# V_15.net
KiCad netlist of a schematic drawn in Altium Designer
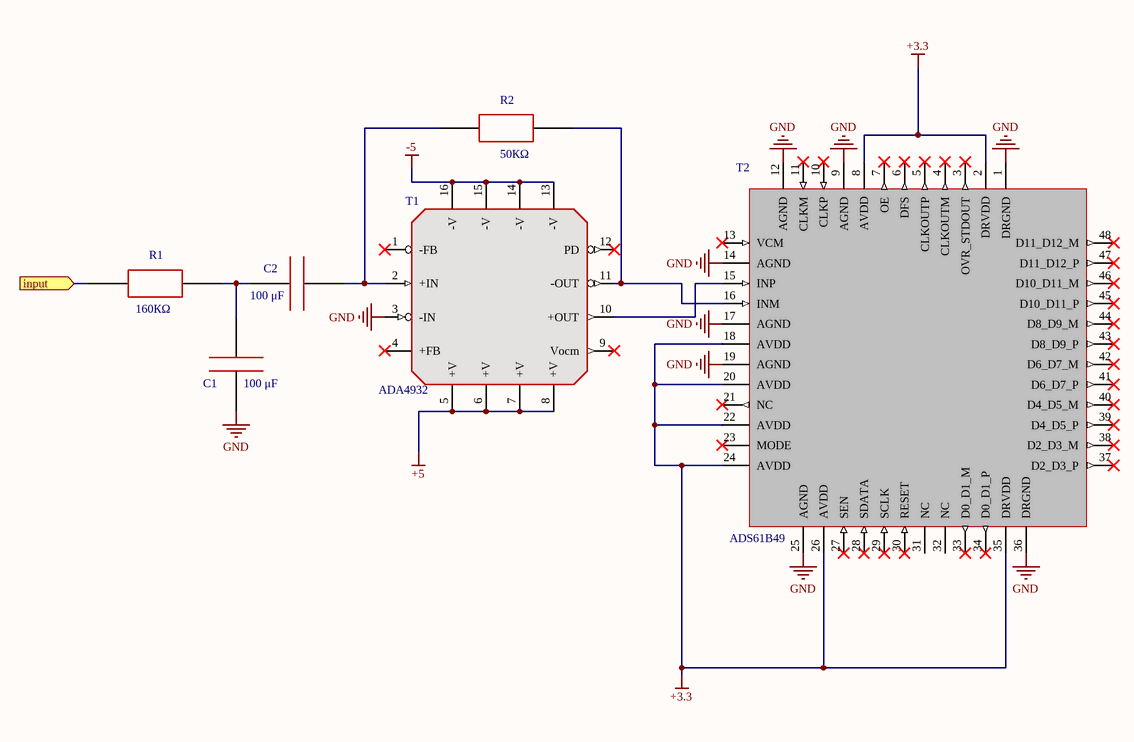
[diagram p0: V_15.SchDoc]

(export (version "E")
  (design (tool "Eeschema 10.0.6"))
  (components
    (comp (ref "C1") (value "100 μF") (footprint "C") (libsource (lib "V_15") (part "Capacitor")))
    (comp (ref "C2") (value "100 μF") (footprint "C") (libsource (lib "V_15") (part "Capacitor")))
    (comp (ref "R1") (value "160КΩ") (footprint "R") (libsource (lib "V_15") (part "Resistor")))
    (comp (ref "R2") (value "50КΩ") (footprint "R") (libsource (lib "V_15") (part "Resistor")))
    (comp (ref "T1") (value "ADA4932") (footprint "ADA4932") (libsource (lib "V_15") (part "ADA4932")))
    (comp (ref "T2") (value "ADS61B49") (footprint "ADS61B49") (libsource (lib "V_15") (part "ADS61B49")))
  )
  (nets
    (net (code "1") (name "+3.3") (class "Default")
      (node (ref "T2") (pin "18") (pinfunction "AVDD_18") (pintype "passive"))
      (node (ref "T2") (pin "2") (pinfunction "DRVDD_2") (pintype "passive"))
      (node (ref "T2") (pin "20") (pinfunction "AVDD_20") (pintype "passive"))
      (node (ref "T2") (pin "22") (pinfunction "AVDD_22") (pintype "passive"))
      (node (ref "T2") (pin "24") (pinfunction "AVDD_24") (pintype "passive"))
      (node (ref "T2") (pin "26") (pinfunction "AVDD_26") (pintype "passive"))
      (node (ref "T2") (pin "35") (pinfunction "DRVDD_35") (pintype "passive"))
      (node (ref "T2") (pin "8") (pinfunction "AVDD_8") (pintype "passive"))
    )
    (net (code "2") (name "+5") (class "Default")
      (node (ref "T1") (pin "5") (pinfunction "+V_5") (pintype "passive"))
      (node (ref "T1") (pin "6") (pinfunction "+V_6") (pintype "passive"))
      (node (ref "T1") (pin "7") (pinfunction "+V_7") (pintype "passive"))
      (node (ref "T1") (pin "8") (pinfunction "+V_8") (pintype "passive"))
    )
    (net (code "3") (name "-5") (class "Default")
      (node (ref "T1") (pin "13") (pinfunction "-V_13") (pintype "passive"))
      (node (ref "T1") (pin "14") (pinfunction "-V_14") (pintype "passive"))
      (node (ref "T1") (pin "15") (pinfunction "-V_15") (pintype "passive"))
      (node (ref "T1") (pin "16") (pinfunction "-V_16") (pintype "passive"))
    )
    (net (code "4") (name "/input") (class "Default")
      (node (ref "R1") (pin "0") (pinfunction "0_0") (pintype "passive"))
    )
    (net (code "5") (name "GND") (class "Default")
      (node (ref "C1") (pin "3") (pinfunction "3_3") (pintype "passive"))
      (node (ref "T1") (pin "3") (pinfunction "-IN_3") (pintype "input"))
      (node (ref "T2") (pin "1") (pinfunction "DRGND_1") (pintype "passive"))
      (node (ref "T2") (pin "12") (pinfunction "AGND_12") (pintype "passive"))
      (node (ref "T2") (pin "14") (pinfunction "AGND_14") (pintype "passive"))
      (node (ref "T2") (pin "17") (pinfunction "AGND_17") (pintype "passive"))
      (node (ref "T2") (pin "19") (pinfunction "AGND_19") (pintype "passive"))
      (node (ref "T2") (pin "25") (pinfunction "AGND_25") (pintype "passive"))
      (node (ref "T2") (pin "36") (pinfunction "DRGND_36") (pintype "passive"))
      (node (ref "T2") (pin "9") (pinfunction "AGND_9") (pintype "passive"))
    )
    (net (code "6") (name "Net-(C1-Pad2)") (class "Default")
      (node (ref "C1") (pin "2") (pinfunction "2_2") (pintype "passive"))
      (node (ref "C2") (pin "3") (pinfunction "3_3") (pintype "passive"))
      (node (ref "R1") (pin "1") (pinfunction "1_1") (pintype "passive"))
    )
    (net (code "7") (name "Net-(T1-+IN)") (class "Default")
      (node (ref "C2") (pin "2") (pinfunction "2_2") (pintype "passive"))
      (node (ref "R2") (pin "0") (pinfunction "0_0") (pintype "passive"))
      (node (ref "T1") (pin "2") (pinfunction "+IN_2") (pintype "input"))
    )
    (net (code "8") (name "Net-(T1-+OUT)") (class "Default")
      (node (ref "T1") (pin "10") (pinfunction "+OUT_10") (pintype "output"))
      (node (ref "T2") (pin "15") (pinfunction "INP_15") (pintype "input"))
    )
    (net (code "9") (name "Net-(T1--OUT)") (class "Default")
      (node (ref "R2") (pin "1") (pinfunction "1_1") (pintype "passive"))
      (node (ref "T1") (pin "11") (pinfunction "-OUT_11") (pintype "output"))
      (node (ref "T2") (pin "16") (pinfunction "INM_16") (pintype "input"))
    )
    (net (code "10") (name "unconnected-(T1-+FB-Pad4)") (class "Default")
      (node (ref "T1") (pin "4") (pinfunction "+FB_4") (pintype "passive+no_connect"))
    )
    (net (code "11") (name "unconnected-(T1--FB-Pad1)") (class "Default")
      (node (ref "T1") (pin "1") (pinfunction "-FB_1") (pintype "passive+no_connect"))
    )
    (net (code "12") (name "unconnected-(T1-PD-Pad12)") (class "Default")
      (node (ref "T1") (pin "12") (pinfunction "PD_12") (pintype "output+no_connect"))
    )
    (net (code "13") (name "unconnected-(T1-Vocm-Pad9)") (class "Default")
      (node (ref "T1") (pin "9") (pinfunction "Vocm_9") (pintype "output+no_connect"))
    )
    (net (code "14") (name "unconnected-(T2-CLKM-Pad11)") (class "Default")
      (node (ref "T2") (pin "11") (pinfunction "CLKM_11") (pintype "input+no_connect"))
    )
    (net (code "15") (name "unconnected-(T2-CLKOUTM-Pad4)") (class "Default")
      (node (ref "T2") (pin "4") (pinfunction "CLKOUTM_4") (pintype "output+no_connect"))
    )
    (net (code "16") (name "unconnected-(T2-CLKOUTP-Pad5)") (class "Default")
      (node (ref "T2") (pin "5") (pinfunction "CLKOUTP_5") (pintype "output+no_connect"))
    )
    (net (code "17") (name "unconnected-(T2-CLKP-Pad10)") (class "Default")
      (node (ref "T2") (pin "10") (pinfunction "CLKP_10") (pintype "input+no_connect"))
    )
    (net (code "18") (name "unconnected-(T2-D0_D1_M-Pad33)") (class "Default")
      (node (ref "T2") (pin "33") (pinfunction "D0_D1_M_33") (pintype "output+no_connect"))
    )
    (net (code "19") (name "unconnected-(T2-D0_D1_P-Pad34)") (class "Default")
      (node (ref "T2") (pin "34") (pinfunction "D0_D1_P_34") (pintype "output+no_connect"))
    )
    (net (code "20") (name "unconnected-(T2-D2_D3_M-Pad38)") (class "Default")
      (node (ref "T2") (pin "38") (pinfunction "D2_D3_M_38") (pintype "output+no_connect"))
    )
    (net (code "21") (name "unconnected-(T2-D2_D3_P-Pad37)") (class "Default")
      (node (ref "T2") (pin "37") (pinfunction "D2_D3_P_37") (pintype "output+no_connect"))
    )
    (net (code "22") (name "unconnected-(T2-D4_D5_M-Pad40)") (class "Default")
      (node (ref "T2") (pin "40") (pinfunction "D4_D5_M_40") (pintype "output+no_connect"))
    )
    (net (code "23") (name "unconnected-(T2-D4_D5_P-Pad39)") (class "Default")
      (node (ref "T2") (pin "39") (pinfunction "D4_D5_P_39") (pintype "output+no_connect"))
    )
    (net (code "24") (name "unconnected-(T2-D6_D7_M-Pad42)") (class "Default")
      (node (ref "T2") (pin "42") (pinfunction "D6_D7_M_42") (pintype "output+no_connect"))
    )
    (net (code "25") (name "unconnected-(T2-D6_D7_P-Pad41)") (class "Default")
      (node (ref "T2") (pin "41") (pinfunction "D6_D7_P_41") (pintype "output+no_connect"))
    )
    (net (code "26") (name "unconnected-(T2-D8_D9_M-Pad44)") (class "Default")
      (node (ref "T2") (pin "44") (pinfunction "D8_D9_M_44") (pintype "output+no_connect"))
    )
    (net (code "27") (name "unconnected-(T2-D8_D9_P-Pad43)") (class "Default")
      (node (ref "T2") (pin "43") (pinfunction "D8_D9_P_43") (pintype "output+no_connect"))
    )
    (net (code "28") (name "unconnected-(T2-D10_D11_M-Pad46)") (class "Default")
      (node (ref "T2") (pin "46") (pinfunction "D10_D11_M_46") (pintype "output+no_connect"))
    )
    (net (code "29") (name "unconnected-(T2-D10_D11_P-Pad45)") (class "Default")
      (node (ref "T2") (pin "45") (pinfunction "D10_D11_P_45") (pintype "output+no_connect"))
    )
    (net (code "30") (name "unconnected-(T2-D11_D12_M-Pad48)") (class "Default")
      (node (ref "T2") (pin "48") (pinfunction "D11_D12_M_48") (pintype "output+no_connect"))
    )
    (net (code "31") (name "unconnected-(T2-D11_D12_P-Pad47)") (class "Default")
      (node (ref "T2") (pin "47") (pinfunction "D11_D12_P_47") (pintype "output+no_connect"))
    )
    (net (code "32") (name "unconnected-(T2-DFS-Pad6)") (class "Default")
      (node (ref "T2") (pin "6") (pinfunction "DFS_6") (pintype "output+no_connect"))
    )
    (net (code "33") (name "unconnected-(T2-MODE-Pad23)") (class "Default")
      (node (ref "T2") (pin "23") (pinfunction "MODE_23") (pintype "passive+no_connect"))
    )
    (net (code "34") (name "unconnected-(T2-NC-Pad21)") (class "Default")
      (node (ref "T2") (pin "21") (pinfunction "NC_21") (pintype "output+no_connect"))
    )
    (net (code "35") (name "unconnected-(T2-NC-Pad31)") (class "Default")
      (node (ref "T2") (pin "31") (pinfunction "NC_31") (pintype "passive"))
    )
    (net (code "36") (name "unconnected-(T2-NC-Pad32)") (class "Default")
      (node (ref "T2") (pin "32") (pinfunction "NC_32") (pintype "passive"))
    )
    (net (code "37") (name "unconnected-(T2-OE-Pad7)") (class "Default")
      (node (ref "T2") (pin "7") (pinfunction "OE_7") (pintype "output+no_connect"))
    )
    (net (code "38") (name "unconnected-(T2-OVR_STDOUT-Pad3)") (class "Default")
      (node (ref "T2") (pin "3") (pinfunction "OVR_STDOUT_3") (pintype "output+no_connect"))
    )
    (net (code "39") (name "unconnected-(T2-RESET-Pad30)") (class "Default")
      (node (ref "T2") (pin "30") (pinfunction "RESET_30") (pintype "input+no_connect"))
    )
    (net (code "40") (name "unconnected-(T2-SCLK-Pad29)") (class "Default")
      (node (ref "T2") (pin "29") (pinfunction "SCLK_29") (pintype "input+no_connect"))
    )
    (net (code "41") (name "unconnected-(T2-SDATA-Pad28)") (class "Default")
      (node (ref "T2") (pin "28") (pinfunction "SDATA_28") (pintype "input+no_connect"))
    )
    (net (code "42") (name "unconnected-(T2-SEN-Pad27)") (class "Default")
      (node (ref "T2") (pin "27") (pinfunction "SEN_27") (pintype "input+no_connect"))
    )
    (net (code "43") (name "unconnected-(T2-VCM-Pad13)") (class "Default")
      (node (ref "T2") (pin "13") (pinfunction "VCM_13") (pintype "input+no_connect"))
    )
  )
)
